# 1.net
KiCad netlist of a schematic drawn in Altium Designer
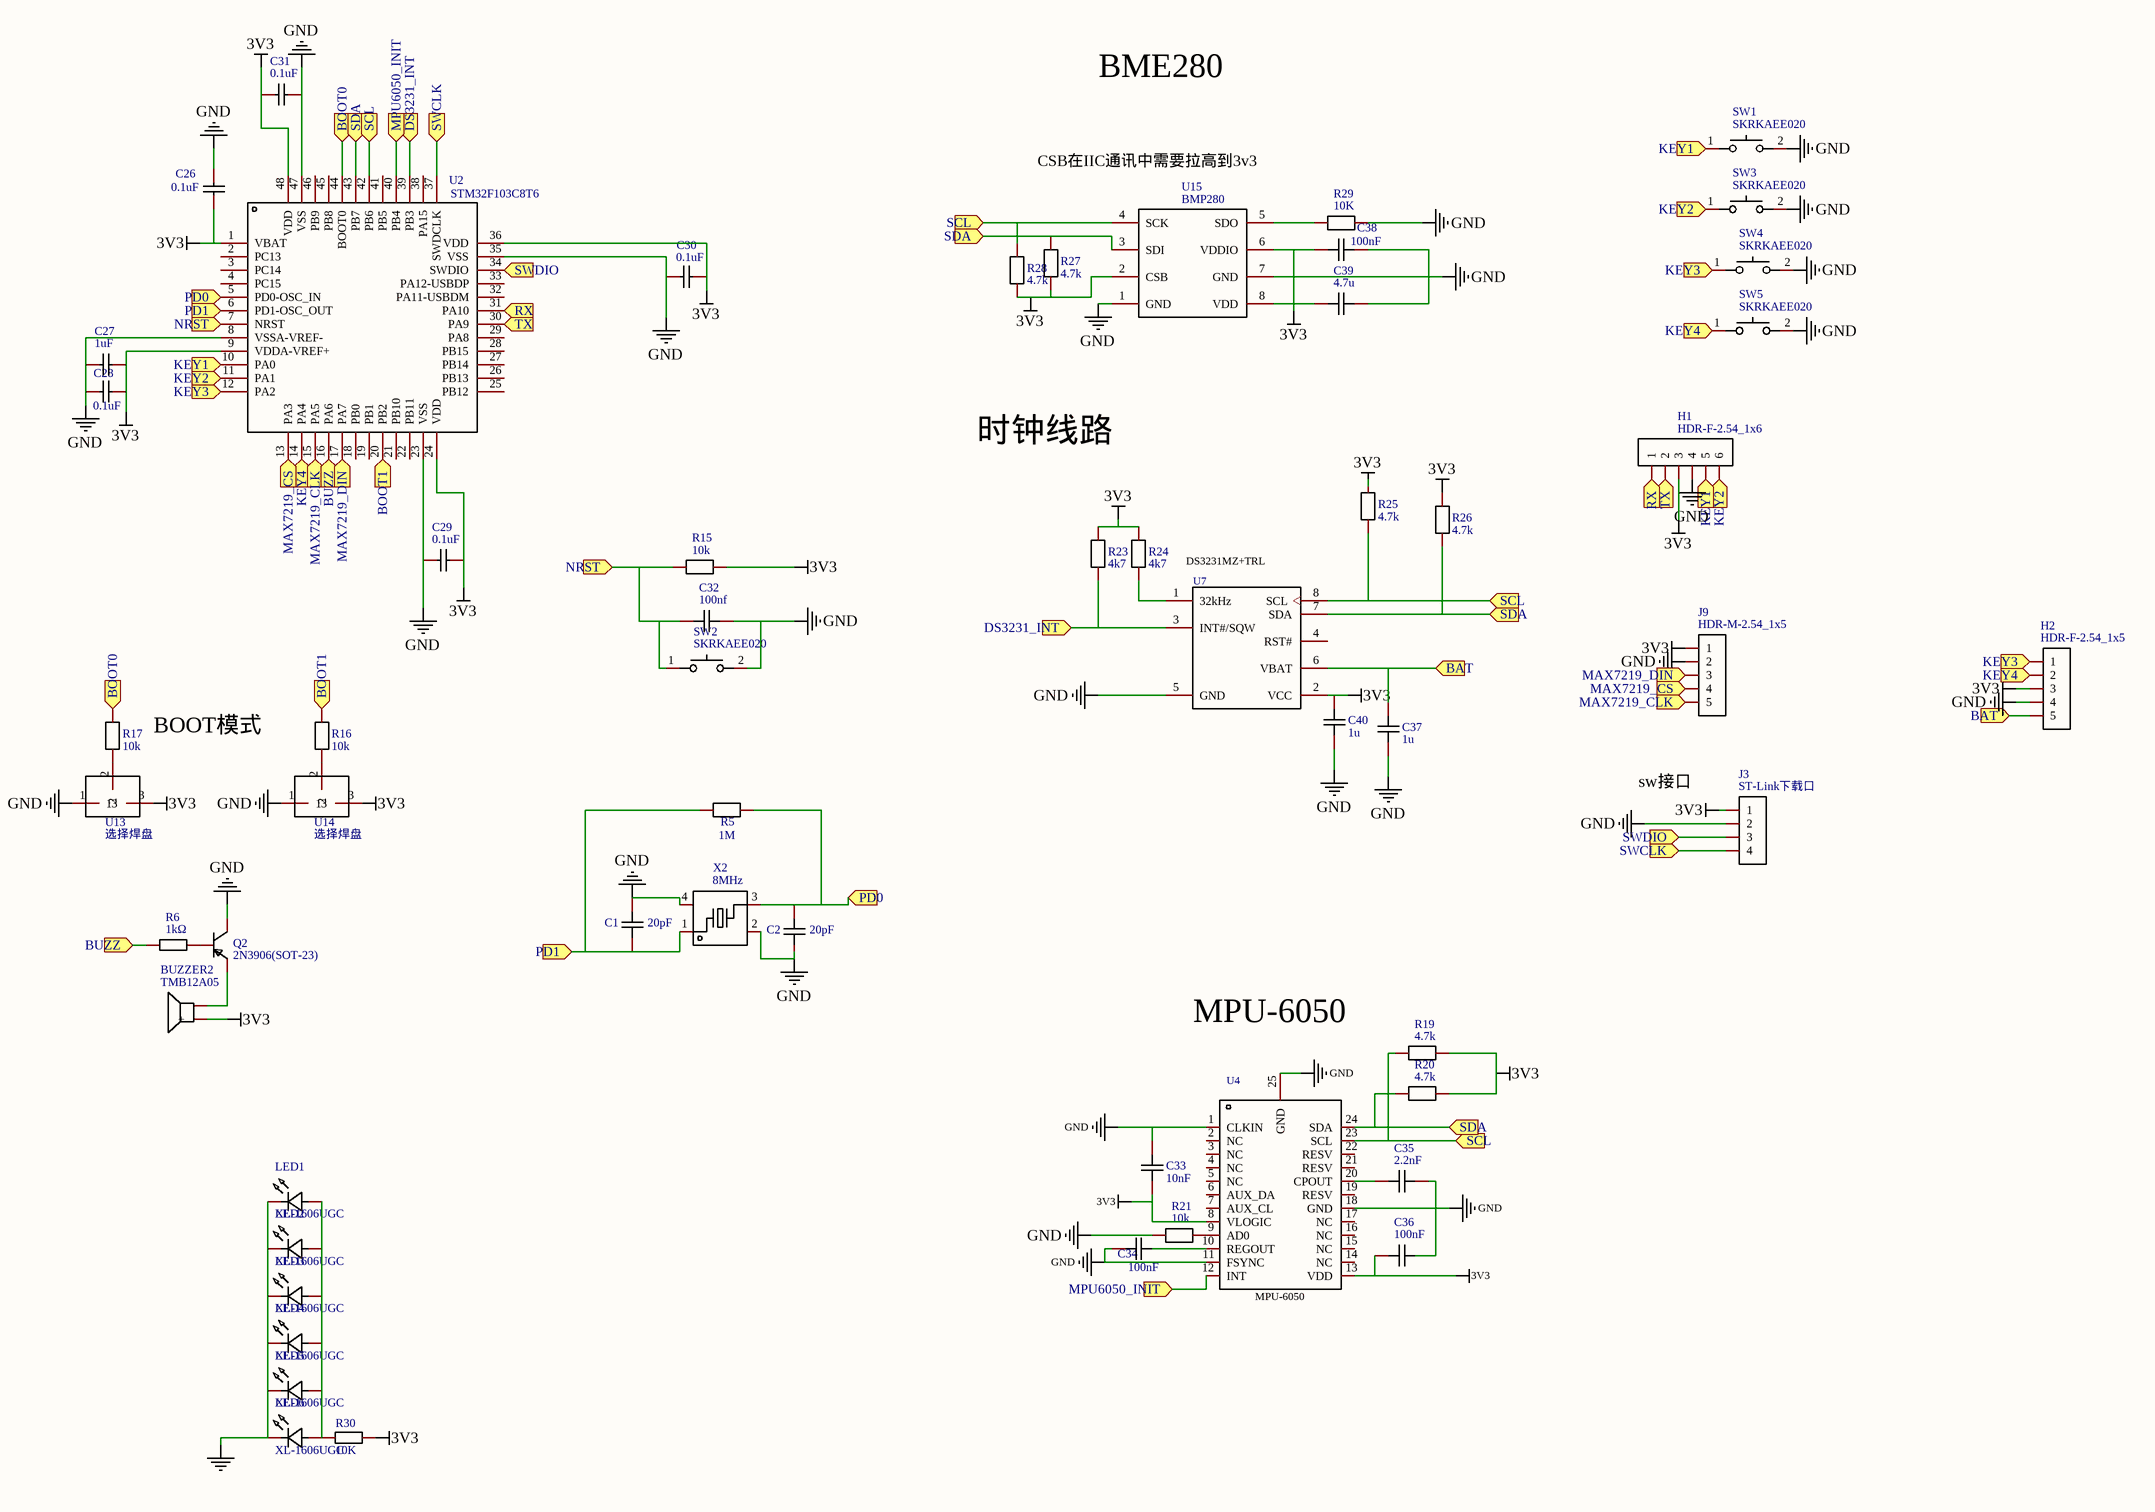
[diagram p0: 1_主控电路.schdoc]

(export (version "E")
  (design (tool "Eeschema 10.0.6"))
  (components
    (comp (ref "1M")
      (value "R5")
      (fields (field (name "NAME") "R5"))
      (libsource (lib "altium-import") (part "root_0_R5_"))
    )
    (comp (ref "BUZZER2")
      (value "TMB12A05")
      (fields (field (name "NAME") "TMB12A05") (field (name "MANUFACTURER") "HNDZ"))
      (libsource (lib "altium-import") (part "root_2_TMB12A05_"))
    )
    (comp (ref "C1")
      (value "20pF")
      (fields (field (name "NAME") "20pF"))
      (libsource (lib "altium-import") (part "root_1_20pF_"))
    )
    (comp (ref "C2")
      (value "20pF")
      (fields (field (name "NAME") "20pF"))
      (libsource (lib "altium-import") (part "root_1_20pF_"))
    )
    (comp (ref "C26")
      (value "0.1uF")
      (fields
        (field (name "NAME") "0.1uF")
        (field (name "MANUFACTURER PART") "TCC0603X7R104K500CT")
        (field (name "MANUFACTURER") "CCTC")
      )
      (libsource (lib "altium-import") (part "root_0_TCC0603X7R104K500CT_"))
    )
    (comp (ref "C27")
      (value "1uF")
      (fields
        (field (name "NAME") "1uF")
        (field (name "MANUFACTURER PART") "TCC0603X7R104K500CT")
        (field (name "MANUFACTURER") "CCTC")
      )
      (libsource (lib "altium-import") (part "root_1_TCC0603X7R104K500CT_"))
    )
    (comp (ref "C28")
      (value "0.1uF")
      (fields
        (field (name "NAME") "0.1uF")
        (field (name "MANUFACTURER PART") "TCC0603X7R104K500CT")
        (field (name "MANUFACTURER") "CCTC")
      )
      (libsource (lib "altium-import") (part "root_1_TCC0603X7R104K500CT_"))
    )
    (comp (ref "C29")
      (value "0.1uF")
      (fields
        (field (name "NAME") "0.1uF")
        (field (name "MANUFACTURER PART") "TCC0603X7R104K500CT")
        (field (name "MANUFACTURER") "CCTC")
      )
      (libsource (lib "altium-import") (part "root_3_TCC0603X7R104K500CT_"))
    )
    (comp (ref "C30")
      (value "0.1uF")
      (fields
        (field (name "NAME") "0.1uF")
        (field (name "MANUFACTURER PART") "TCC0603X7R104K500CT")
        (field (name "MANUFACTURER") "CCTC")
      )
      (libsource (lib "altium-import") (part "root_1_TCC0603X7R104K500CT_"))
    )
    (comp (ref "C31")
      (value "0.1uF")
      (fields
        (field (name "NAME") "0.1uF")
        (field (name "MANUFACTURER PART") "TCC0603X7R104K500CT")
        (field (name "MANUFACTURER") "CCTC")
      )
      (libsource (lib "altium-import") (part "root_3_TCC0603X7R104K500CT_"))
    )
    (comp (ref "C32")
      (value "100nf")
      (fields (field (name "NAME") "100nf"))
      (libsource (lib "altium-import") (part "root_0_100nf_"))
    )
    (comp (ref "C33")
      (value "10nF")
      (fields (field (name "NAME") "10nF"))
      (libsource (lib "altium-import") (part "root_1_10nF_"))
    )
    (comp (ref "C34")
      (value "100nF")
      (fields (field (name "NAME") "100nF"))
      (libsource (lib "altium-import") (part "root_0_100nF_"))
    )
    (comp (ref "C35")
      (value "2.2nF")
      (fields (field (name "NAME") "2.2nF"))
      (libsource (lib "altium-import") (part "root_0_2.2nF_"))
    )
    (comp (ref "C36")
      (value "100nF")
      (fields (field (name "NAME") "100nF"))
      (libsource (lib "altium-import") (part "root_0_100nF_"))
    )
    (comp (ref "C37")
      (value "1u")
      (fields (field (name "NAME") "1u"))
      (libsource (lib "altium-import") (part "root_1_1u_"))
    )
    (comp (ref "C38")
      (value "100nF")
      (fields (field (name "NAME") "100nF"))
      (libsource (lib "altium-import") (part "root_0_100nF_"))
    )
    (comp (ref "C39")
      (value "4.7u")
      (fields (field (name "NAME") "4.7u"))
      (libsource (lib "altium-import") (part "root_0_4.7u_"))
    )
    (comp (ref "C40")
      (value "1u")
      (fields (field (name "NAME") "1u"))
      (libsource (lib "altium-import") (part "root_1_1u_"))
    )
    (comp (ref "H1")
      (value "HDR-F-2.54_1x6")
      (fields (field (name "NAME") "HDR-F-2.54_1x6"))
      (libsource (lib "altium-import") (part "root_1_HDR-F-2.54_1x6_"))
    )
    (comp (ref "H2")
      (value "HDR-F-2.54_1x5")
      (fields (field (name "NAME") "HDR-F-2.54_1x5"))
      (libsource (lib "altium-import") (part "root_0_HDR-F-2.54_1x5_"))
    )
    (comp (ref "J3")
      (value "ST-Link下载口")
      (fields (field (name "NAME") "ST-Link下载口"))
      (libsource (lib "altium-import") (part "root_0_ST-Link下载口_"))
    )
    (comp (ref "J9")
      (value "HDR-M-2.54_1x5")
      (fields (field (name "NAME") "HDR-M-2.54_1x5"))
      (libsource (lib "altium-import") (part "root_0_HDR-M-2.54_1x5_"))
    )
    (comp (ref "LED1")
      (value "XL-1606UGC")
      (description "发光颜色:翠绿;主波长:520nm~530nm;色温:-;功率:80mW;安装方式:侧贴;")
      (fields (field (name "NAME") "XL-1606UGC") (field (name "MANUFACTURER") "XINGLIGHT(成兴光)"))
      (libsource (lib "altium-import") (part "root_0_XL-1606UGC_"))
    )
    (comp (ref "LED2")
      (value "XL-1606UGC")
      (description "发光颜色:翠绿;主波长:520nm~530nm;色温:-;功率:80mW;安装方式:侧贴;")
      (fields (field (name "NAME") "XL-1606UGC") (field (name "MANUFACTURER") "XINGLIGHT(成兴光)"))
      (libsource (lib "altium-import") (part "root_0_XL-1606UGC_"))
    )
    (comp (ref "LED3")
      (value "XL-1606UGC")
      (description "发光颜色:翠绿;主波长:520nm~530nm;色温:-;功率:80mW;安装方式:侧贴;")
      (fields (field (name "NAME") "XL-1606UGC") (field (name "MANUFACTURER") "XINGLIGHT(成兴光)"))
      (libsource (lib "altium-import") (part "root_0_XL-1606UGC_"))
    )
    (comp (ref "LED4")
      (value "XL-1606UGC")
      (description "发光颜色:翠绿;主波长:520nm~530nm;色温:-;功率:80mW;安装方式:侧贴;")
      (fields (field (name "NAME") "XL-1606UGC") (field (name "MANUFACTURER") "XINGLIGHT(成兴光)"))
      (libsource (lib "altium-import") (part "root_0_XL-1606UGC_"))
    )
    (comp (ref "LED5")
      (value "XL-1606UGC")
      (description "发光颜色:翠绿;主波长:520nm~530nm;色温:-;功率:80mW;安装方式:侧贴;")
      (fields (field (name "NAME") "XL-1606UGC") (field (name "MANUFACTURER") "XINGLIGHT(成兴光)"))
      (libsource (lib "altium-import") (part "root_0_XL-1606UGC_"))
    )
    (comp (ref "LED6")
      (value "XL-1606UGC")
      (description "发光颜色:翠绿;主波长:520nm~530nm;色温:-;功率:80mW;安装方式:侧贴;")
      (fields (field (name "NAME") "XL-1606UGC") (field (name "MANUFACTURER") "XINGLIGHT(成兴光)"))
      (libsource (lib "altium-import") (part "root_0_XL-1606UGC_"))
    )
    (comp (ref "Q2")
      (value "2N3906(SOT-23)")
      (fields
        (field (name "NAME") "2N3906(SOT-23)")
        (field (name "MANUFACTURER") "KEC")
        (field (name "MANUFACTURER PART") "2N3906S-RTK/PS")
      )
      (libsource (lib "altium-import") (part "root_0_2N3906S-RTK/PS_"))
    )
    (comp (ref "R6")
      (value "1kΩ")
      (fields
        (field (name "NAME") "1kΩ")
        (field (name "MANUFACTURER") "FH")
        (field (name "MANUFACTURER PART") "RS-03K102JT")
      )
      (libsource (lib "altium-import") (part "root_0_RS-03K102JT_"))
    )
    (comp (ref "R15")
      (value "10k")
      (fields (field (name "NAME") "10k"))
      (libsource (lib "altium-import") (part "root_0_10k_"))
    )
    (comp (ref "R16")
      (value "10k")
      (fields (field (name "NAME") "10k"))
      (libsource (lib "altium-import") (part "root_1_10k_"))
    )
    (comp (ref "R17")
      (value "10k")
      (fields (field (name "NAME") "10k"))
      (libsource (lib "altium-import") (part "root_1_10k_"))
    )
    (comp (ref "R19")
      (value "4.7k")
      (fields (field (name "NAME") "4.7k"))
      (libsource (lib "altium-import") (part "root_0_4.7k_"))
    )
    (comp (ref "R20")
      (value "4.7k")
      (fields (field (name "NAME") "4.7k"))
      (libsource (lib "altium-import") (part "root_0_4.7k_"))
    )
    (comp (ref "R21")
      (value "10k")
      (fields (field (name "NAME") "10k"))
      (libsource (lib "altium-import") (part "root_0_10k_"))
    )
    (comp (ref "R23")
      (value "4k7")
      (fields (field (name "NAME") "4k7"))
      (libsource (lib "altium-import") (part "root_1_4k7_"))
    )
    (comp (ref "R24")
      (value "4k7")
      (fields (field (name "NAME") "4k7"))
      (libsource (lib "altium-import") (part "root_1_4k7_"))
    )
    (comp (ref "R25")
      (value "4.7k")
      (fields (field (name "NAME") "4.7k"))
      (libsource (lib "altium-import") (part "root_1_4.7k_"))
    )
    (comp (ref "R26")
      (value "4.7k")
      (fields (field (name "NAME") "4.7k"))
      (libsource (lib "altium-import") (part "root_1_4.7k_"))
    )
    (comp (ref "R27")
      (value "4.7k")
      (fields (field (name "NAME") "4.7k"))
      (libsource (lib "altium-import") (part "root_1_4.7k_"))
    )
    (comp (ref "R28")
      (value "4.7k")
      (fields (field (name "NAME") "4.7k"))
      (libsource (lib "altium-import") (part "root_1_4.7k_"))
    )
    (comp (ref "R29")
      (value "10K")
      (fields (field (name "NAME") "10K"))
      (libsource (lib "altium-import") (part "root_0_10K_"))
    )
    (comp (ref "R30")
      (value "10K")
      (fields (field (name "NAME") "10K"))
      (libsource (lib "altium-import") (part "root_0_Res_0603_"))
    )
    (comp (ref "SW1")
      (value "SKRKAEE020")
      (fields (field (name "NAME") "SKRKAEE020") (field (name "MANUFACTURER") "ALPSALPINE(阿尔卑斯阿尔派)"))
      (libsource (lib "altium-import") (part "root_0_SKRKAEE020_"))
    )
    (comp (ref "SW2")
      (value "SKRKAEE020")
      (fields (field (name "NAME") "SKRKAEE020") (field (name "MANUFACTURER") "ALPSALPINE(阿尔卑斯阿尔派)"))
      (libsource (lib "altium-import") (part "root_0_SKRKAEE020_"))
    )
    (comp (ref "SW3")
      (value "SKRKAEE020")
      (fields (field (name "NAME") "SKRKAEE020") (field (name "MANUFACTURER") "ALPSALPINE(阿尔卑斯阿尔派)"))
      (libsource (lib "altium-import") (part "root_0_SKRKAEE020_"))
    )
    (comp (ref "SW4")
      (value "SKRKAEE020")
      (fields (field (name "NAME") "SKRKAEE020") (field (name "MANUFACTURER") "ALPSALPINE(阿尔卑斯阿尔派)"))
      (libsource (lib "altium-import") (part "root_0_SKRKAEE020_"))
    )
    (comp (ref "SW5")
      (value "SKRKAEE020")
      (fields (field (name "NAME") "SKRKAEE020") (field (name "MANUFACTURER") "ALPSALPINE(阿尔卑斯阿尔派)"))
      (libsource (lib "altium-import") (part "root_0_SKRKAEE020_"))
    )
    (comp (ref "U2")
      (value "STM32F103C8T6")
      (fields
        (field (name "NAME") "STM32F103C8T6")
        (field (name "MANUFACTURER") "MindMotionMicroelectronics")
        (field (name "MANUFACTURER PART") "MM32F103C8T6")
      )
      (libsource (lib "altium-import") (part "root_0_MM32F103C8T6_"))
    )
    (comp (ref "U4")
      (value "MPU-6050")
      (description "三轴加速度计和三轴陀螺仪，工作电压：2.375V3.46V")
      (fields (field (name "MANUFACTURER") "TDK InvenSense(应美盛)"))
      (libsource (lib "altium-import") (part "root_0_MPU-6050_"))
    )
    (comp (ref "U7")
      (value "DS3231MZ+TRL")
      (description "时钟芯片类型:Clock/Calendar;存储器容量:-;时间格式:HH:MM:SS (12/24 hr);日期格式:YY-MM-DD-dd;接口类型:I2C, 2-Wire Serial;")
      (fields (field (name "MANUFACTURER") "MAXIM(美信)"))
      (libsource (lib "altium-import") (part "root_0_DS3231MZ+TRL_"))
    )
    (comp (ref "U13")
      (value "选择焊盘")
      (fields (field (name "NAME") "选择焊盘"))
      (libsource (lib "altium-import") (part "root_0_选择焊盘_"))
    )
    (comp (ref "U14")
      (value "选择焊盘")
      (fields (field (name "NAME") "选择焊盘"))
      (libsource (lib "altium-import") (part "root_0_选择焊盘_"))
    )
    (comp (ref "U15")
      (value "BMP280")
      (fields (field (name "NAME") "BMP280") (field (name "MANUFACTURER") "Bosch(博世)"))
      (libsource (lib "altium-import") (part "root_2_BMP280_"))
    )
    (comp (ref "X2")
      (value "8MHz")
      (fields
        (field (name "NAME") "8MHz")
        (field (name "MANUFACTURER") "YXC(扬兴晶振)")
        (field (name "MANUFACTURER PART") "X32258MOB4SI")
      )
      (libsource (lib "altium-import") (part "root_0_X32258MOB4SI_"))
    )
  )
  (nets
    (net (code "1") (name "/BAT") (class "Default")
      (node (ref "C37") (pin "2") (pinfunction "2_2") (pintype "passive"))
      (node (ref "H2") (pin "5") (pinfunction "5_5") (pintype "passive"))
      (node (ref "U7") (pin "6") (pinfunction "VBAT_6") (pintype "passive"))
    )
    (net (code "2") (name "/BOOT0") (class "Default")
      (node (ref "R17") (pin "2") (pinfunction "2_2") (pintype "passive"))
      (node (ref "U2") (pin "44") (pinfunction "BOOT0_44") (pintype "passive"))
    )
    (net (code "3") (name "/BOOT1") (class "Default")
      (node (ref "R16") (pin "2") (pinfunction "2_2") (pintype "passive"))
      (node (ref "U2") (pin "20") (pinfunction "PB2_20") (pintype "passive"))
    )
    (net (code "4") (name "/BUZZ") (class "Default")
      (node (ref "R6") (pin "1") (pinfunction "1_1") (pintype "passive"))
      (node (ref "U2") (pin "16") (pinfunction "PA6_16") (pintype "passive"))
    )
    (net (code "5") (name "/DS3231_INT") (class "Default")
      (node (ref "R23") (pin "1") (pinfunction "1_1") (pintype "passive"))
      (node (ref "U2") (pin "39") (pinfunction "PB3_39") (pintype "passive"))
      (node (ref "U7") (pin "3") (pinfunction "INT#/SQW_3") (pintype "passive"))
    )
    (net (code "6") (name "/KEY1") (class "Default")
      (node (ref "H1") (pin "5") (pinfunction "5_5") (pintype "passive"))
      (node (ref "SW1") (pin "1") (pinfunction "1_1") (pintype "passive"))
      (node (ref "U2") (pin "10") (pinfunction "PA0_10") (pintype "passive"))
    )
    (net (code "7") (name "/KEY2") (class "Default")
      (node (ref "H1") (pin "6") (pinfunction "6_6") (pintype "passive"))
      (node (ref "SW3") (pin "1") (pinfunction "1_1") (pintype "passive"))
      (node (ref "U2") (pin "11") (pinfunction "PA1_11") (pintype "passive"))
    )
    (net (code "8") (name "/KEY3") (class "Default")
      (node (ref "H2") (pin "1") (pinfunction "1_1") (pintype "passive"))
      (node (ref "SW4") (pin "1") (pinfunction "1_1") (pintype "passive"))
      (node (ref "U2") (pin "12") (pinfunction "PA2_12") (pintype "passive"))
    )
    (net (code "9") (name "/KEY4") (class "Default")
      (node (ref "H2") (pin "2") (pinfunction "2_2") (pintype "passive"))
      (node (ref "SW5") (pin "1") (pinfunction "1_1") (pintype "passive"))
      (node (ref "U2") (pin "14") (pinfunction "PA4_14") (pintype "passive"))
    )
    (net (code "10") (name "/MAX7219_CLK") (class "Default")
      (node (ref "J9") (pin "5") (pinfunction "5_5") (pintype "passive"))
      (node (ref "U2") (pin "15") (pinfunction "PA5_15") (pintype "passive"))
    )
    (net (code "11") (name "/MAX7219_CS") (class "Default")
      (node (ref "J9") (pin "4") (pinfunction "4_4") (pintype "passive"))
      (node (ref "U2") (pin "13") (pinfunction "PA3_13") (pintype "passive"))
    )
    (net (code "12") (name "/MAX7219_DIN") (class "Default")
      (node (ref "J9") (pin "3") (pinfunction "3_3") (pintype "passive"))
      (node (ref "U2") (pin "17") (pinfunction "PA7_17") (pintype "passive"))
    )
    (net (code "13") (name "/MPU6050_INIT") (class "Default")
      (node (ref "U2") (pin "40") (pinfunction "PB4_40") (pintype "passive"))
      (node (ref "U4") (pin "12") (pinfunction "INT_12") (pintype "passive"))
    )
    (net (code "14") (name "/NRST") (class "Default")
      (node (ref "C32") (pin "1") (pinfunction "1_1") (pintype "passive"))
      (node (ref "R15") (pin "1") (pinfunction "1_1") (pintype "passive"))
      (node (ref "SW2") (pin "1") (pinfunction "1_1") (pintype "passive"))
      (node (ref "U2") (pin "7") (pinfunction "NRST_7") (pintype "passive"))
    )
    (net (code "15") (name "/PD0") (class "Default")
      (node (ref "1M") (pin "2") (pinfunction "2_2") (pintype "passive"))
      (node (ref "C2") (pin "2") (pinfunction "2_2") (pintype "passive"))
      (node (ref "U2") (pin "5") (pinfunction "PD0-OSC_IN_5") (pintype "passive"))
      (node (ref "X2") (pin "3") (pinfunction "3_3") (pintype "passive"))
    )
    (net (code "16") (name "/PD1") (class "Default")
      (node (ref "1M") (pin "1") (pinfunction "1_1") (pintype "passive"))
      (node (ref "C1") (pin "1") (pinfunction "1_1") (pintype "passive"))
      (node (ref "U2") (pin "6") (pinfunction "PD1-OSC_OUT_6") (pintype "passive"))
      (node (ref "X2") (pin "1") (pinfunction "1_1") (pintype "passive"))
    )
    (net (code "17") (name "/RX") (class "Default")
      (node (ref "H1") (pin "1") (pinfunction "1_1") (pintype "passive"))
      (node (ref "U2") (pin "31") (pinfunction "PA10_31") (pintype "passive"))
    )
    (net (code "18") (name "/SCL") (class "Default")
      (node (ref "R19") (pin "1") (pinfunction "1_1") (pintype "passive"))
      (node (ref "R25") (pin "1") (pinfunction "1_1") (pintype "passive"))
      (node (ref "R28") (pin "2") (pinfunction "2_2") (pintype "passive"))
      (node (ref "U15") (pin "4") (pinfunction "SCK_4") (pintype "passive"))
      (node (ref "U2") (pin "42") (pinfunction "PB6_42") (pintype "passive"))
      (node (ref "U4") (pin "23") (pinfunction "SCL_23") (pintype "passive"))
      (node (ref "U7") (pin "8") (pinfunction "SCL_8") (pintype "passive"))
    )
    (net (code "19") (name "/SDA") (class "Default")
      (node (ref "R20") (pin "1") (pinfunction "1_1") (pintype "passive"))
      (node (ref "R26") (pin "1") (pinfunction "1_1") (pintype "passive"))
      (node (ref "R27") (pin "2") (pinfunction "2_2") (pintype "passive"))
      (node (ref "U15") (pin "3") (pinfunction "SDI_3") (pintype "passive"))
      (node (ref "U2") (pin "43") (pinfunction "PB7_43") (pintype "passive"))
      (node (ref "U4") (pin "24") (pinfunction "SDA_24") (pintype "passive"))
      (node (ref "U7") (pin "7") (pinfunction "SDA_7") (pintype "passive"))
    )
    (net (code "20") (name "/SWCLK") (class "Default")
      (node (ref "J3") (pin "4") (pinfunction "4_4") (pintype "passive"))
      (node (ref "U2") (pin "37") (pinfunction "SWDCLK_37") (pintype "passive"))
    )
    (net (code "21") (name "/SWDIO") (class "Default")
      (node (ref "J3") (pin "3") (pinfunction "3_3") (pintype "passive"))
      (node (ref "U2") (pin "34") (pinfunction "SWDIO_34") (pintype "passive"))
    )
    (net (code "22") (name "/TX") (class "Default")
      (node (ref "H1") (pin "2") (pinfunction "2_2") (pintype "passive"))
      (node (ref "U2") (pin "30") (pinfunction "PA9_30") (pintype "passive"))
    )
    (net (code "23") (name "3V3") (class "Default")
      (node (ref "BUZZER2") (pin "1") (pinfunction "+_1") (pintype "passive"))
      (node (ref "C26") (pin "2") (pinfunction "2_2") (pintype "passive"))
      (node (ref "C27") (pin "2") (pinfunction "2_2") (pintype "passive"))
      (node (ref "C28") (pin "2") (pinfunction "2_2") (pintype "passive"))
      (node (ref "C29") (pin "1") (pinfunction "1_1") (pintype "passive"))
      (node (ref "C30") (pin "2") (pinfunction "2_2") (pintype "passive"))
      (node (ref "C31") (pin "2") (pinfunction "2_2") (pintype "passive"))
      (node (ref "C33") (pin "1") (pinfunction "1_1") (pintype "passive"))
      (node (ref "C36") (pin "1") (pinfunction "1_1") (pintype "passive"))
      (node (ref "C38") (pin "1") (pinfunction "1_1") (pintype "passive"))
      (node (ref "C39") (pin "1") (pinfunction "1_1") (pintype "passive"))
      (node (ref "C40") (pin "2") (pinfunction "2_2") (pintype "passive"))
      (node (ref "H1") (pin "3") (pinfunction "3_3") (pintype "passive"))
      (node (ref "H2") (pin "3") (pinfunction "3_3") (pintype "passive"))
      (node (ref "J3") (pin "1") (pinfunction "1_1") (pintype "passive"))
      (node (ref "J9") (pin "1") (pinfunction "1_1") (pintype "passive"))
      (node (ref "R15") (pin "2") (pinfunction "2_2") (pintype "passive"))
      (node (ref "R19") (pin "2") (pinfunction "2_2") (pintype "passive"))
      (node (ref "R20") (pin "2") (pinfunction "2_2") (pintype "passive"))
      (node (ref "R23") (pin "2") (pinfunction "2_2") (pintype "passive"))
      (node (ref "R24") (pin "2") (pinfunction "2_2") (pintype "passive"))
      (node (ref "R25") (pin "2") (pinfunction "2_2") (pintype "passive"))
      (node (ref "R26") (pin "2") (pinfunction "2_2") (pintype "passive"))
      (node (ref "R27") (pin "1") (pinfunction "1_1") (pintype "passive"))
      (node (ref "R28") (pin "1") (pinfunction "1_1") (pintype "passive"))
      (node (ref "R30") (pin "2") (pinfunction "2_2") (pintype "passive"))
      (node (ref "U13") (pin "3") (pinfunction "3_3") (pintype "passive"))
      (node (ref "U14") (pin "3") (pinfunction "3_3") (pintype "passive"))
      (node (ref "U15") (pin "2") (pinfunction "CSB_2") (pintype "passive"))
      (node (ref "U15") (pin "6") (pinfunction "VDDIO_6") (pintype "passive"))
      (node (ref "U15") (pin "8") (pinfunction "VDD_8") (pintype "passive"))
      (node (ref "U2") (pin "1") (pinfunction "VBAT_1") (pintype "passive"))
      (node (ref "U2") (pin "24") (pinfunction "VDD_24") (pintype "passive"))
      (node (ref "U2") (pin "36") (pinfunction "VDD_36") (pintype "passive"))
      (node (ref "U2") (pin "48") (pinfunction "VDD_48") (pintype "passive"))
      (node (ref "U2") (pin "9") (pinfunction "VDDA-VREF+_9") (pintype "passive"))
      (node (ref "U4") (pin "13") (pinfunction "VDD_13") (pintype "passive"))
      (node (ref "U4") (pin "8") (pinfunction "VLOGIC_8") (pintype "passive"))
      (node (ref "U7") (pin "2") (pinfunction "VCC_2") (pintype "passive"))
    )
    (net (code "24") (name "<NO NET>") (class "Default")
      (node (ref "LED1") (pin "2") (pinfunction "K_2") (pintype "passive"))
      (node (ref "LED2") (pin "2") (pinfunction "K_2") (pintype "passive"))
      (node (ref "LED3") (pin "2") (pinfunction "K_2") (pintype "passive"))
      (node (ref "LED4") (pin "2") (pinfunction "K_2") (pintype "passive"))
      (node (ref "LED5") (pin "2") (pinfunction "K_2") (pintype "passive"))
      (node (ref "LED6") (pin "2") (pinfunction "K_2") (pintype "passive"))
    )
    (net (code "25") (name "GND") (class "Default")
      (node (ref "C1") (pin "2") (pinfunction "2_2") (pintype "passive"))
      (node (ref "C2") (pin "1") (pinfunction "1_1") (pintype "passive"))
      (node (ref "C26") (pin "1") (pinfunction "1_1") (pintype "passive"))
      (node (ref "C27") (pin "1") (pinfunction "1_1") (pintype "passive"))
      (node (ref "C28") (pin "1") (pinfunction "1_1") (pintype "passive"))
      (node (ref "C29") (pin "2") (pinfunction "2_2") (pintype "passive"))
      (node (ref "C30") (pin "1") (pinfunction "1_1") (pintype "passive"))
      (node (ref "C31") (pin "1") (pinfunction "1_1") (pintype "passive"))
      (node (ref "C32") (pin "2") (pinfunction "2_2") (pintype "passive"))
      (node (ref "C33") (pin "2") (pinfunction "2_2") (pintype "passive"))
      (node (ref "C34") (pin "1") (pinfunction "1_1") (pintype "passive"))
      (node (ref "C35") (pin "2") (pinfunction "2_2") (pintype "passive"))
      (node (ref "C36") (pin "2") (pinfunction "2_2") (pintype "passive"))
      (node (ref "C37") (pin "1") (pinfunction "1_1") (pintype "passive"))
      (node (ref "C38") (pin "2") (pinfunction "2_2") (pintype "passive"))
      (node (ref "C39") (pin "2") (pinfunction "2_2") (pintype "passive"))
      (node (ref "C40") (pin "1") (pinfunction "1_1") (pintype "passive"))
      (node (ref "H1") (pin "4") (pinfunction "4_4") (pintype "passive"))
      (node (ref "H2") (pin "4") (pinfunction "4_4") (pintype "passive"))
      (node (ref "J3") (pin "2") (pinfunction "2_2") (pintype "passive"))
      (node (ref "J9") (pin "2") (pinfunction "2_2") (pintype "passive"))
      (node (ref "Q2") (pin "3") (pinfunction "C_3") (pintype "passive"))
      (node (ref "R21") (pin "1") (pinfunction "1_1") (pintype "passive"))
      (node (ref "R29") (pin "2") (pinfunction "2_2") (pintype "passive"))
      (node (ref "SW1") (pin "2") (pinfunction "2_2") (pintype "passive"))
      (node (ref "SW2") (pin "2") (pinfunction "2_2") (pintype "passive"))
      (node (ref "SW3") (pin "2") (pinfunction "2_2") (pintype "passive"))
      (node (ref "SW4") (pin "2") (pinfunction "2_2") (pintype "passive"))
      (node (ref "SW5") (pin "2") (pinfunction "2_2") (pintype "passive"))
      (node (ref "U13") (pin "1") (pinfunction "1_1") (pintype "passive"))
      (node (ref "U14") (pin "1") (pinfunction "1_1") (pintype "passive"))
      (node (ref "U15") (pin "1") (pinfunction "GND_1") (pintype "passive"))
      (node (ref "U15") (pin "7") (pinfunction "GND_7") (pintype "passive"))
      (node (ref "U2") (pin "23") (pinfunction "VSS_23") (pintype "passive"))
      (node (ref "U2") (pin "35") (pinfunction "VSS_35") (pintype "passive"))
      (node (ref "U2") (pin "47") (pinfunction "VSS_47") (pintype "passive"))
      (node (ref "U2") (pin "8") (pinfunction "VSSA-VREF-_8") (pintype "passive"))
      (node (ref "U4") (pin "1") (pinfunction "CLKIN_1") (pintype "passive"))
      (node (ref "U4") (pin "11") (pinfunction "FSYNC_11") (pintype "passive"))
      (node (ref "U4") (pin "18") (pinfunction "GND_18") (pintype "passive"))
      (node (ref "U4") (pin "25") (pinfunction "GND_25") (pintype "passive"))
      (node (ref "U7") (pin "5") (pinfunction "GND_5") (pintype "passive"))
      (node (ref "X2") (pin "2") (pinfunction "GND_2") (pintype "passive"))
      (node (ref "X2") (pin "4") (pinfunction "GND_4") (pintype "passive"))
    )
    (net (code "26") (name "Net-(LED1-A)") (class "Default")
      (node (ref "LED1") (pin "1") (pinfunction "A_1") (pintype "passive"))
      (node (ref "LED2") (pin "1") (pinfunction "A_1") (pintype "passive"))
      (node (ref "LED3") (pin "1") (pinfunction "A_1") (pintype "passive"))
      (node (ref "LED4") (pin "1") (pinfunction "A_1") (pintype "passive"))
      (node (ref "LED5") (pin "1") (pinfunction "A_1") (pintype "passive"))
      (node (ref "LED6") (pin "1") (pinfunction "A_1") (pintype "passive"))
      (node (ref "R30") (pin "1") (pinfunction "1_1") (pintype "passive"))
    )
    (net (code "27") (name "Net-(Q2-B)") (class "Default")
      (node (ref "Q2") (pin "2") (pinfunction "B_2") (pintype "passive"))
      (node (ref "R6") (pin "2") (pinfunction "2_2") (pintype "passive"))
    )
    (net (code "28") (name "Net-(Q2-E)") (class "Default")
      (node (ref "BUZZER2") (pin "2") (pinfunction "2_2") (pintype "passive"))
      (node (ref "Q2") (pin "1") (pinfunction "E_1") (pintype "passive"))
    )
    (net (code "29") (name "Net-(R16-Pad1)") (class "Default")
      (node (ref "R16") (pin "1") (pinfunction "1_1") (pintype "passive"))
      (node (ref "U14") (pin "2") (pinfunction "2_2") (pintype "passive"))
    )
    (net (code "30") (name "Net-(R17-Pad1)") (class "Default")
      (node (ref "R17") (pin "1") (pinfunction "1_1") (pintype "passive"))
      (node (ref "U13") (pin "2") (pinfunction "2_2") (pintype "passive"))
    )
    (net (code "31") (name "Net-(U4-AD0)") (class "Default")
      (node (ref "R21") (pin "2") (pinfunction "2_2") (pintype "passive"))
      (node (ref "U4") (pin "9") (pinfunction "AD0_9") (pintype "passive"))
    )
    (net (code "32") (name "Net-(U4-CPOUT)") (class "Default")
      (node (ref "C35") (pin "1") (pinfunction "1_1") (pintype "passive"))
      (node (ref "U4") (pin "20") (pinfunction "CPOUT_20") (pintype "passive"))
    )
    (net (code "33") (name "Net-(U4-REGOUT)") (class "Default")
      (node (ref "C34") (pin "2") (pinfunction "2_2") (pintype "passive"))
      (node (ref "U4") (pin "10") (pinfunction "REGOUT_10") (pintype "passive"))
    )
    (net (code "34") (name "Net-(U7-32kHz)") (class "Default")
      (node (ref "R24") (pin "1") (pinfunction "1_1") (pintype "passive"))
      (node (ref "U7") (pin "1") (pinfunction "32kHz_1") (pintype "passive"))
    )
    (net (code "35") (name "Net-(U15-SDO)") (class "Default")
      (node (ref "R29") (pin "1") (pinfunction "1_1") (pintype "passive"))
      (node (ref "U15") (pin "5") (pinfunction "SDO_5") (pintype "passive"))
    )
    (net (code "36") (name "unconnected-(U2-PA8-Pad29)") (class "Default")
      (node (ref "U2") (pin "29") (pinfunction "PA8_29") (pintype "passive"))
    )
    (net (code "37") (name "unconnected-(U2-PA11-USBDM-Pad32)") (class "Default")
      (node (ref "U2") (pin "32") (pinfunction "PA11-USBDM_32") (pintype "passive"))
    )
    (net (code "38") (name "unconnected-(U2-PA12-USBDP-Pad33)") (class "Default")
      (node (ref "U2") (pin "33") (pinfunction "PA12-USBDP_33") (pintype "passive"))
    )
    (net (code "39") (name "unconnected-(U2-PA15-Pad38)") (class "Default")
      (node (ref "U2") (pin "38") (pinfunction "PA15_38") (pintype "passive"))
    )
    (net (code "40") (name "unconnected-(U2-PB0-Pad18)") (class "Default")
      (node (ref "U2") (pin "18") (pinfunction "PB0_18") (pintype "passive"))
    )
    (net (code "41") (name "unconnected-(U2-PB1-Pad19)") (class "Default")
      (node (ref "U2") (pin "19") (pinfunction "PB1_19") (pintype "passive"))
    )
    (net (code "42") (name "unconnected-(U2-PB5-Pad41)") (class "Default")
      (node (ref "U2") (pin "41") (pinfunction "PB5_41") (pintype "passive"))
    )
    (net (code "43") (name "unconnected-(U2-PB8-Pad45)") (class "Default")
      (node (ref "U2") (pin "45") (pinfunction "PB8_45") (pintype "passive"))
    )
    (net (code "44") (name "unconnected-(U2-PB9-Pad46)") (class "Default")
      (node (ref "U2") (pin "46") (pinfunction "PB9_46") (pintype "passive"))
    )
    (net (code "45") (name "unconnected-(U2-PB10-Pad21)") (class "Default")
      (node (ref "U2") (pin "21") (pinfunction "PB10_21") (pintype "passive"))
    )
    (net (code "46") (name "unconnected-(U2-PB11-Pad22)") (class "Default")
      (node (ref "U2") (pin "22") (pinfunction "PB11_22") (pintype "passive"))
    )
    (net (code "47") (name "unconnected-(U2-PB12-Pad25)") (class "Default")
      (node (ref "U2") (pin "25") (pinfunction "PB12_25") (pintype "passive"))
    )
    (net (code "48") (name "unconnected-(U2-PB13-Pad26)") (class "Default")
      (node (ref "U2") (pin "26") (pinfunction "PB13_26") (pintype "passive"))
    )
    (net (code "49") (name "unconnected-(U2-PB14-Pad27)") (class "Default")
      (node (ref "U2") (pin "27") (pinfunction "PB14_27") (pintype "passive"))
    )
    (net (code "50") (name "unconnected-(U2-PB15-Pad28)") (class "Default")
      (node (ref "U2") (pin "28") (pinfunction "PB15_28") (pintype "passive"))
    )
    (net (code "51") (name "unconnected-(U2-PC13-Pad2)") (class "Default")
      (node (ref "U2") (pin "2") (pinfunction "PC13_2") (pintype "passive"))
    )
    (net (code "52") (name "unconnected-(U2-PC14-Pad3)") (class "Default")
      (node (ref "U2") (pin "3") (pinfunction "PC14_3") (pintype "passive"))
    )
    (net (code "53") (name "unconnected-(U2-PC15-Pad4)") (class "Default")
      (node (ref "U2") (pin "4") (pinfunction "PC15_4") (pintype "passive"))
    )
    (net (code "54") (name "unconnected-(U4-AUX_CL-Pad7)") (class "Default")
      (node (ref "U4") (pin "7") (pinfunction "AUX_CL_7") (pintype "passive"))
    )
    (net (code "55") (name "unconnected-(U4-AUX_DA-Pad6)") (class "Default")
      (node (ref "U4") (pin "6") (pinfunction "AUX_DA_6") (pintype "passive"))
    )
    (net (code "56") (name "unconnected-(U4-NC-Pad2)") (class "Default")
      (node (ref "U4") (pin "2") (pinfunction "NC_2") (pintype "passive"))
    )
    (net (code "57") (name "unconnected-(U4-NC-Pad3)") (class "Default")
      (node (ref "U4") (pin "3") (pinfunction "NC_3") (pintype "passive"))
    )
    (net (code "58") (name "unconnected-(U4-NC-Pad4)") (class "Default")
      (node (ref "U4") (pin "4") (pinfunction "NC_4") (pintype "passive"))
    )
    (net (code "59") (name "unconnected-(U4-NC-Pad5)") (class "Default")
      (node (ref "U4") (pin "5") (pinfunction "NC_5") (pintype "passive"))
    )
    (net (code "60") (name "unconnected-(U4-NC-Pad14)") (class "Default")
      (node (ref "U4") (pin "14") (pinfunction "NC_14") (pintype "passive"))
    )
    (net (code "61") (name "unconnected-(U4-NC-Pad15)") (class "Default")
      (node (ref "U4") (pin "15") (pinfunction "NC_15") (pintype "passive"))
    )
    (net (code "62") (name "unconnected-(U4-NC-Pad16)") (class "Default")
      (node (ref "U4") (pin "16") (pinfunction "NC_16") (pintype "passive"))
    )
    (net (code "63") (name "unconnected-(U4-NC-Pad17)") (class "Default")
      (node (ref "U4") (pin "17") (pinfunction "NC_17") (pintype "passive"))
    )
    (net (code "64") (name "unconnected-(U4-RESV-Pad19)") (class "Default")
      (node (ref "U4") (pin "19") (pinfunction "RESV_19") (pintype "passive"))
    )
    (net (code "65") (name "unconnected-(U4-RESV-Pad21)") (class "Default")
      (node (ref "U4") (pin "21") (pinfunction "RESV_21") (pintype "passive"))
    )
    (net (code "66") (name "unconnected-(U4-RESV-Pad22)") (class "Default")
      (node (ref "U4") (pin "22") (pinfunction "RESV_22") (pintype "passive"))
    )
    (net (code "67") (name "unconnected-(U7-RST#-Pad4)") (class "Default")
      (node (ref "U7") (pin "4") (pinfunction "RST#_4") (pintype "passive"))
    )
  )
)
